# PoweredAudio.net
KiCad netlist of a schematic drawn in EAGLE
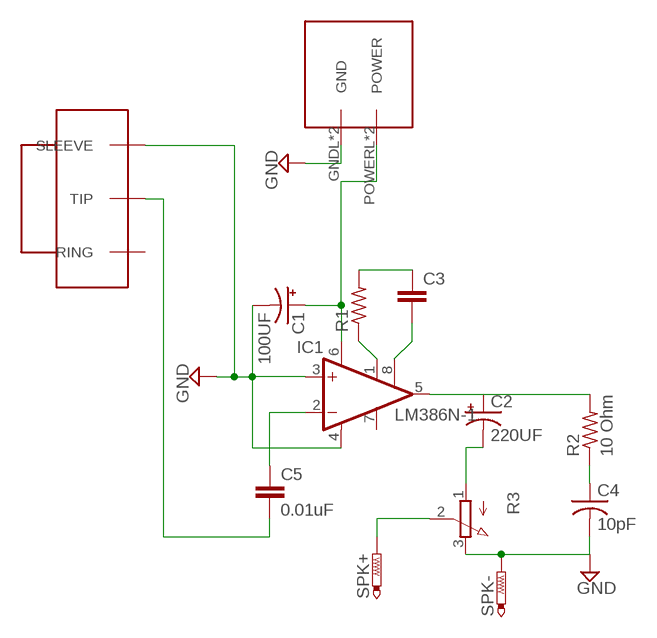
[diagram p0: schematic, sheet 1]

(export (version "E")
  (design (tool "Eeschema 10.0.6"))
  (components
    (comp (ref "C1")
      (value "100UF")
      (footprint "eagle-import:E2,5-7")
      (libsource (lib "eagle-import") (part "CPOL-USE2.5-7"))
    )
    (comp (ref "C2")
      (value "220UF")
      (footprint "eagle-import:E2,5-7")
      (libsource (lib "eagle-import") (part "CPOL-USE2.5-7"))
    )
    (comp (ref "C3")
      (value "C-EU025-025X050")
      (footprint "eagle-import:C025-025X050")
      (libsource (lib "eagle-import") (part "C-EU025-025X050"))
    )
    (comp (ref "C4")
      (value "10pF")
      (footprint "eagle-import:C1206")
      (libsource (lib "eagle-import") (part "C-USC1206"))
    )
    (comp (ref "C5")
      (value "0.01uF")
      (footprint "eagle-import:C2.5-2")
      (libsource (lib "eagle-import") (part "C2.5/2"))
    )
    (comp (ref "IC1")
      (value "LM386N-1")
      (footprint "eagle-import:DIL08")
      (libsource (lib "eagle-import") (part "LM386?-N1"))
    )
    (comp (ref "R1")
      (value "R-US_0204/5")
      (footprint "eagle-import:0204_5")
      (libsource (lib "eagle-import") (part "resistor_R-US_0204/5"))
    )
    (comp (ref "R2")
      (value "10 Ohm")
      (footprint "eagle-import:M1206")
      (libsource (lib "eagle-import") (part "R-US_M1206"))
    )
    (comp (ref "R3")
      (value "3RP/1610N")
      (footprint "eagle-import:3RP_1610N")
      (libsource (lib "eagle-import") (part "3RP/1610N"))
    )
    (comp (ref "SPK+")
      (value "PTR1PAD1-13Y")
      (footprint "eagle-import:P1-13Y")
      (libsource (lib "eagle-import") (part "PTR1PAD1-13Y"))
    )
    (comp (ref "SPK-")
      (value "PTR1PAD1-13Y")
      (footprint "eagle-import:P1-13Y")
      (libsource (lib "eagle-import") (part "PTR1PAD1-13Y"))
    )
    (comp (ref "U$1")
      (value "SJ-352X")
      (footprint "eagle-import:SJ1-352XN")
      (libsource (lib "eagle-import") (part "SJ-352X"))
    )
    (comp (ref "U$2")
      (value "2X2-MOLEX")
      (footprint "eagle-import:2X2MOLEX")
      (libsource (lib "eagle-import") (part "2X2-MOLEX"))
    )
  )
  (nets
    (net (code "1") (name "GND") (class "Default")
      (node (ref "C1") (pin "-") (pinfunction "-_-") (pintype "passive"))
      (node (ref "C4") (pin "2") (pinfunction "2_2") (pintype "passive"))
      (node (ref "IC1") (pin "3") (pinfunction "+IN_3") (pintype "input"))
      (node (ref "IC1") (pin "4") (pinfunction "GND_4") (pintype "power_in"))
      (node (ref "R3") (pin "3") (pinfunction "E_3") (pintype "passive"))
      (node (ref "SPK-") (pin "TP") (pinfunction "TP_TP") (pintype "input"))
      (node (ref "U$1") (pin "SLEEVE") (pinfunction "SLEEVE_SLEEVE") (pintype "bidirectional"))
      (node (ref "U$2") (pin "GNDL") (pinfunction "GND_GNDL") (pintype "bidirectional"))
      (node (ref "U$2") (pin "GNDR") (pinfunction "GND_GNDR") (pintype "bidirectional"))
    )
    (net (code "2") (name "Net-(C3-Pad1)") (class "Default")
      (node (ref "C3") (pin "1") (pinfunction "1_1") (pintype "passive"))
      (node (ref "R1") (pin "2") (pinfunction "2_2") (pintype "passive"))
    )
    (net (code "3") (name "Net-(C3-Pad2)") (class "Default")
      (node (ref "C3") (pin "2") (pinfunction "2_2") (pintype "passive"))
      (node (ref "IC1") (pin "8") (pinfunction "GAIN_8") (pintype "passive"))
    )
    (net (code "4") (name "Net-(C4-Pad1)") (class "Default")
      (node (ref "C4") (pin "1") (pinfunction "1_1") (pintype "passive"))
      (node (ref "R2") (pin "1") (pinfunction "1_1") (pintype "passive"))
    )
    (net (code "5") (name "Net-(C5-Pad2)") (class "Default")
      (node (ref "C5") (pin "2") (pinfunction "2_2") (pintype "passive"))
      (node (ref "U$1") (pin "TIP") (pinfunction "TIP_TIP") (pintype "bidirectional"))
    )
    (net (code "6") (name "Net-(IC1--IN)") (class "Default")
      (node (ref "C5") (pin "1") (pinfunction "1_1") (pintype "passive"))
      (node (ref "IC1") (pin "2") (pinfunction "-IN_2") (pintype "input"))
    )
    (net (code "7") (name "Net-(IC1-GAIN-Pad1)") (class "Default")
      (node (ref "IC1") (pin "1") (pinfunction "GAIN_1") (pintype "passive"))
      (node (ref "R1") (pin "1") (pinfunction "1_1") (pintype "passive"))
    )
    (net (code "8") (name "Net-(IC1-OUT)") (class "Default")
      (node (ref "C2") (pin "+") (pinfunction "+_+") (pintype "passive"))
      (node (ref "IC1") (pin "5") (pinfunction "OUT_5") (pintype "output"))
      (node (ref "R2") (pin "2") (pinfunction "2_2") (pintype "passive"))
    )
    (net (code "9") (name "Net-(IC1-VS)") (class "Default")
      (node (ref "C1") (pin "+") (pinfunction "+_+") (pintype "passive"))
      (node (ref "IC1") (pin "6") (pinfunction "VS_6") (pintype "power_in"))
      (node (ref "U$2") (pin "POWERL") (pinfunction "POWER_POWERL") (pintype "bidirectional"))
      (node (ref "U$2") (pin "POWERR") (pinfunction "POWER_POWERR") (pintype "bidirectional"))
    )
    (net (code "10") (name "Net-(R3-A)") (class "Default")
      (node (ref "C2") (pin "-") (pinfunction "-_-") (pintype "passive"))
      (node (ref "R3") (pin "1") (pinfunction "A_1") (pintype "passive"))
    )
    (net (code "11") (name "Net-(R3-S)") (class "Default")
      (node (ref "R3") (pin "2") (pinfunction "S_2") (pintype "passive"))
      (node (ref "SPK+") (pin "TP") (pinfunction "TP_TP") (pintype "input"))
    )
    (net (code "12") (name "unconnected-(IC1-BYPASS-Pad7)") (class "Default")
      (node (ref "IC1") (pin "7") (pinfunction "BYPASS_7") (pintype "passive"))
    )
    (net (code "13") (name "unconnected-(U$1-PadRING)") (class "Default")
      (node (ref "U$1") (pin "RING") (pinfunction "RING_RING") (pintype "bidirectional"))
    )
  )
)
